# robot_control_pcb.net
KiCad netlist of a schematic drawn in Altium Designer
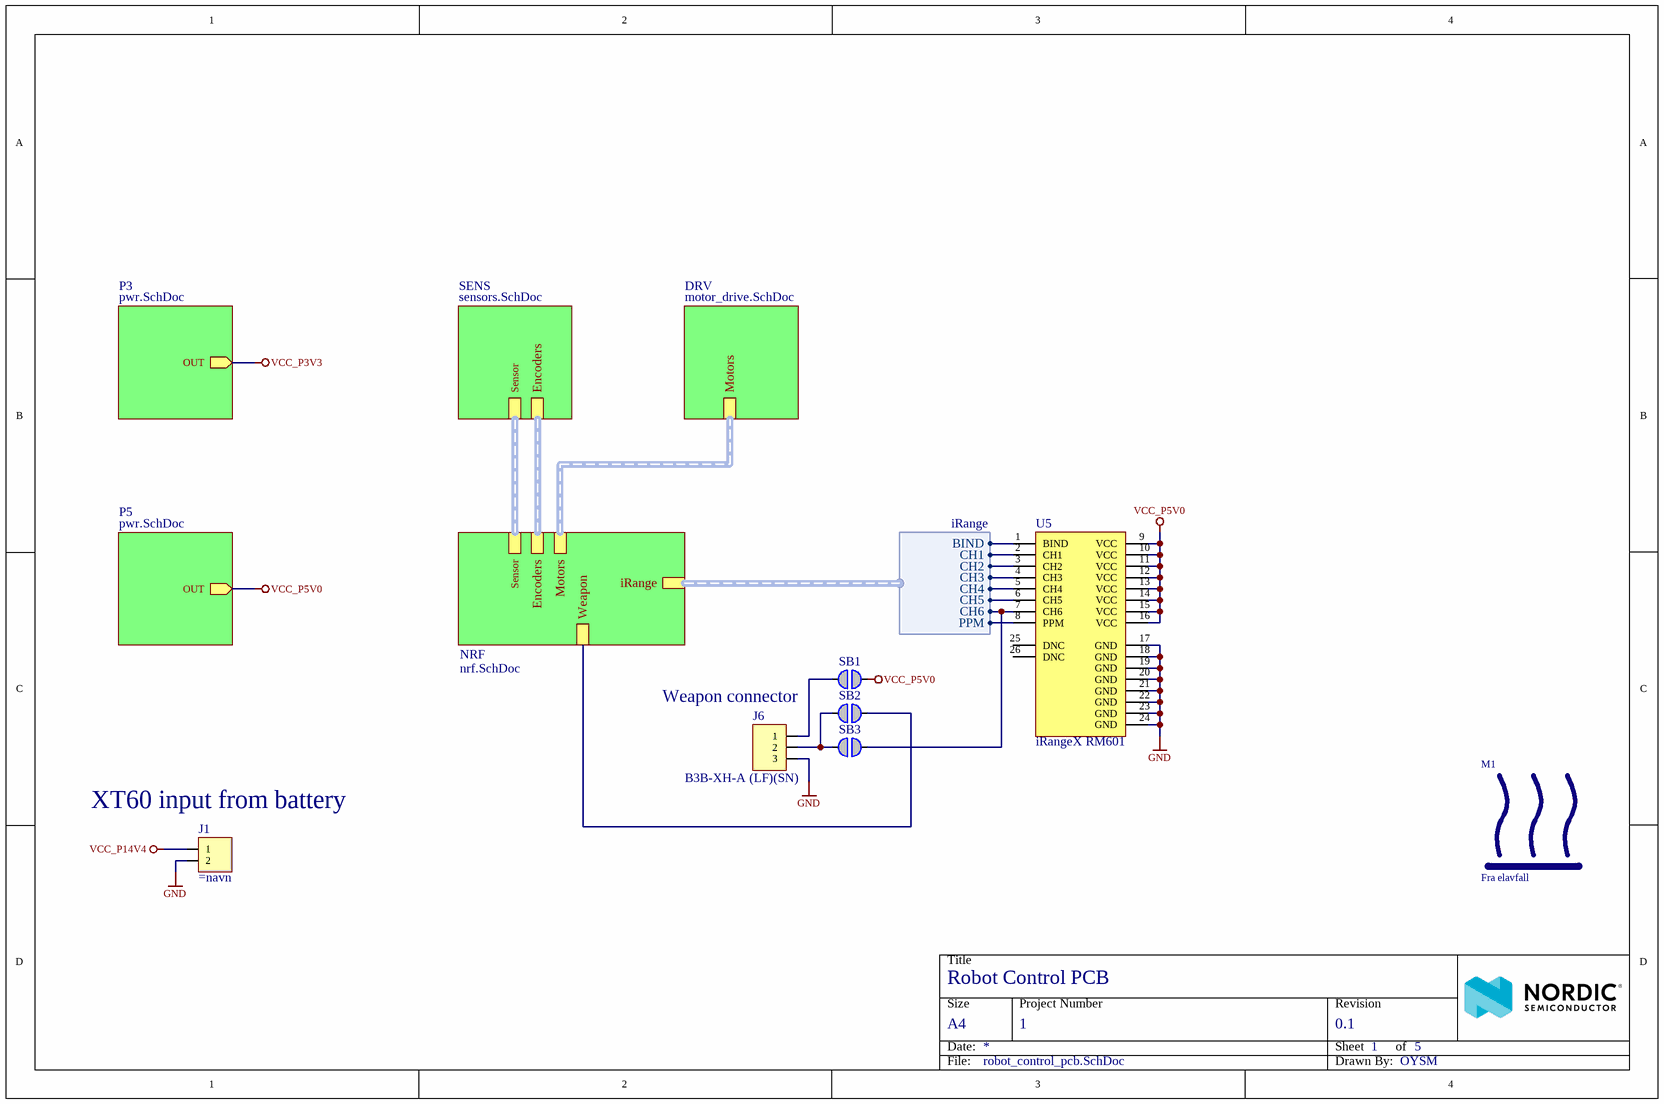
[diagram p0: robot_control_pcb.SchDoc]

(export (version "E")
  (design (tool "Eeschema 10.0.6"))
  (components
    (comp (ref "J1")
      (value "~")
      (footprint "XT60_Male_Vertical")
      (description "For å koble ledninger sammen")
      (libsource (lib "OVLib_64") (part "2PConnector"))
    )
    (comp (ref "J6")
      (value "B3B-XH-A (LF)(SN)")
      (footprint "JST_3P")
      (description "JST 3pin (pris pr. stk.)")
      (libsource (lib "OVLib_64") (part "3PConnector"))
    )
    (comp (ref "M1")
      (value "Fra elavfall")
      (footprint "Heatsink_36x31x09")
      (description "Heatsink")
      (libsource (lib "Heatsink") (part "Heatsink"))
    )
    (comp (ref "SB1")
      (value "Solderbridge")
      (footprint "Solderbridge")
      (fields (field (name "PUBLISHER") "Nordic Semiconductor"))
      (libsource (lib "Nordic Passive DB") (part "SOLDERBRIDGE"))
    )
    (comp (ref "SB2")
      (value "Solderbridge")
      (footprint "Solderbridge")
      (fields (field (name "PUBLISHER") "Nordic Semiconductor"))
      (libsource (lib "Nordic Passive DB") (part "SOLDERBRIDGE"))
    )
    (comp (ref "SB3")
      (value "Solderbridge")
      (footprint "Solderbridge")
      (fields (field (name "PUBLISHER") "Nordic Semiconductor"))
      (libsource (lib "Nordic Passive DB") (part "SOLDERBRIDGE"))
    )
    (comp (ref "U5")
      (value "iRangeX RM601")
      (footprint "iRangeX RM601")
      (libsource (lib "iRangeX RM601") (part "iRangeX RM601"))
    )
  )
  (nets
    (net (code "2") (name "/BIND") (class "Default")
      (node (ref "U5") (pin "1") (pinfunction "BIND_1") (pintype "passive"))
    )
    (net (code "3") (name "/CH1") (class "Default")
      (node (ref "U5") (pin "2") (pinfunction "CH1_2") (pintype "passive"))
    )
    (net (code "4") (name "/CH2") (class "Default")
      (node (ref "U5") (pin "3") (pinfunction "CH2_3") (pintype "passive"))
    )
    (net (code "5") (name "/CH3") (class "Default")
      (node (ref "U5") (pin "4") (pinfunction "CH3_4") (pintype "passive"))
    )
    (net (code "6") (name "/CH4") (class "Default")
      (node (ref "U5") (pin "5") (pinfunction "CH4_5") (pintype "passive"))
    )
    (net (code "7") (name "/CH5") (class "Default")
      (node (ref "U5") (pin "6") (pinfunction "CH5_6") (pintype "passive"))
    )
    (net (code "8") (name "/CH6") (class "Default")
      (node (ref "SB3") (pin "1") (pinfunction "0_1") (pintype "passive"))
      (node (ref "U5") (pin "7") (pinfunction "CH6_7") (pintype "passive"))
    )
    (net (code "11") (name "/PPM") (class "Default")
      (node (ref "U5") (pin "8") (pinfunction "PPM_8") (pintype "passive"))
    )
    (net (code "13") (name "/Weapon") (class "Default")
      (node (ref "SB2") (pin "1") (pinfunction "0_1") (pintype "passive"))
    )
    (net (code "15") (name "GND") (class "Default")
      (node (ref "J1") (pin "2") (pinfunction "2_2") (pintype "passive"))
      (node (ref "J6") (pin "3") (pinfunction "3_3") (pintype "passive"))
      (node (ref "U5") (pin "17") (pinfunction "GND_17") (pintype "passive"))
      (node (ref "U5") (pin "18") (pinfunction "GND_18") (pintype "passive"))
      (node (ref "U5") (pin "19") (pinfunction "GND_19") (pintype "passive"))
      (node (ref "U5") (pin "20") (pinfunction "GND_20") (pintype "passive"))
      (node (ref "U5") (pin "21") (pinfunction "GND_21") (pintype "passive"))
      (node (ref "U5") (pin "22") (pinfunction "GND_22") (pintype "passive"))
      (node (ref "U5") (pin "23") (pinfunction "GND_23") (pintype "passive"))
      (node (ref "U5") (pin "24") (pinfunction "GND_24") (pintype "passive"))
    )
    (net (code "16") (name "Net-(SB1-1)") (class "Default")
      (node (ref "J6") (pin "1") (pinfunction "1_1") (pintype "passive"))
      (node (ref "SB1") (pin "2") (pinfunction "1_2") (pintype "passive"))
    )
    (net (code "17") (name "Net-(SB2-1)") (class "Default")
      (node (ref "J6") (pin "2") (pinfunction "2_2") (pintype "passive"))
      (node (ref "SB2") (pin "2") (pinfunction "1_2") (pintype "passive"))
      (node (ref "SB3") (pin "2") (pinfunction "1_2") (pintype "passive"))
    )
    (net (code "19") (name "VCC_P5V0") (class "Default")
      (node (ref "SB1") (pin "1") (pinfunction "0_1") (pintype "passive"))
      (node (ref "U5") (pin "10") (pinfunction "VCC_10") (pintype "passive"))
      (node (ref "U5") (pin "11") (pinfunction "VCC_11") (pintype "passive"))
      (node (ref "U5") (pin "12") (pinfunction "VCC_12") (pintype "passive"))
      (node (ref "U5") (pin "13") (pinfunction "VCC_13") (pintype "passive"))
      (node (ref "U5") (pin "14") (pinfunction "VCC_14") (pintype "passive"))
      (node (ref "U5") (pin "15") (pinfunction "VCC_15") (pintype "passive"))
      (node (ref "U5") (pin "16") (pinfunction "VCC_16") (pintype "passive"))
      (node (ref "U5") (pin "9") (pinfunction "VCC_9") (pintype "passive"))
    )
    (net (code "20") (name "VCC_P14V4") (class "Default")
      (node (ref "J1") (pin "1") (pinfunction "1_1") (pintype "passive"))
    )
    (net (code "21") (name "unconnected-(U5-DNC-Pad25)") (class "Default")
      (node (ref "U5") (pin "25") (pinfunction "DNC_25") (pintype "passive"))
    )
    (net (code "22") (name "unconnected-(U5-DNC-Pad26)") (class "Default")
      (node (ref "U5") (pin "26") (pinfunction "DNC_26") (pintype "passive"))
    )
  )
)
